# Accelerometer_revb.net
KiCad netlist of a schematic drawn in EAGLE
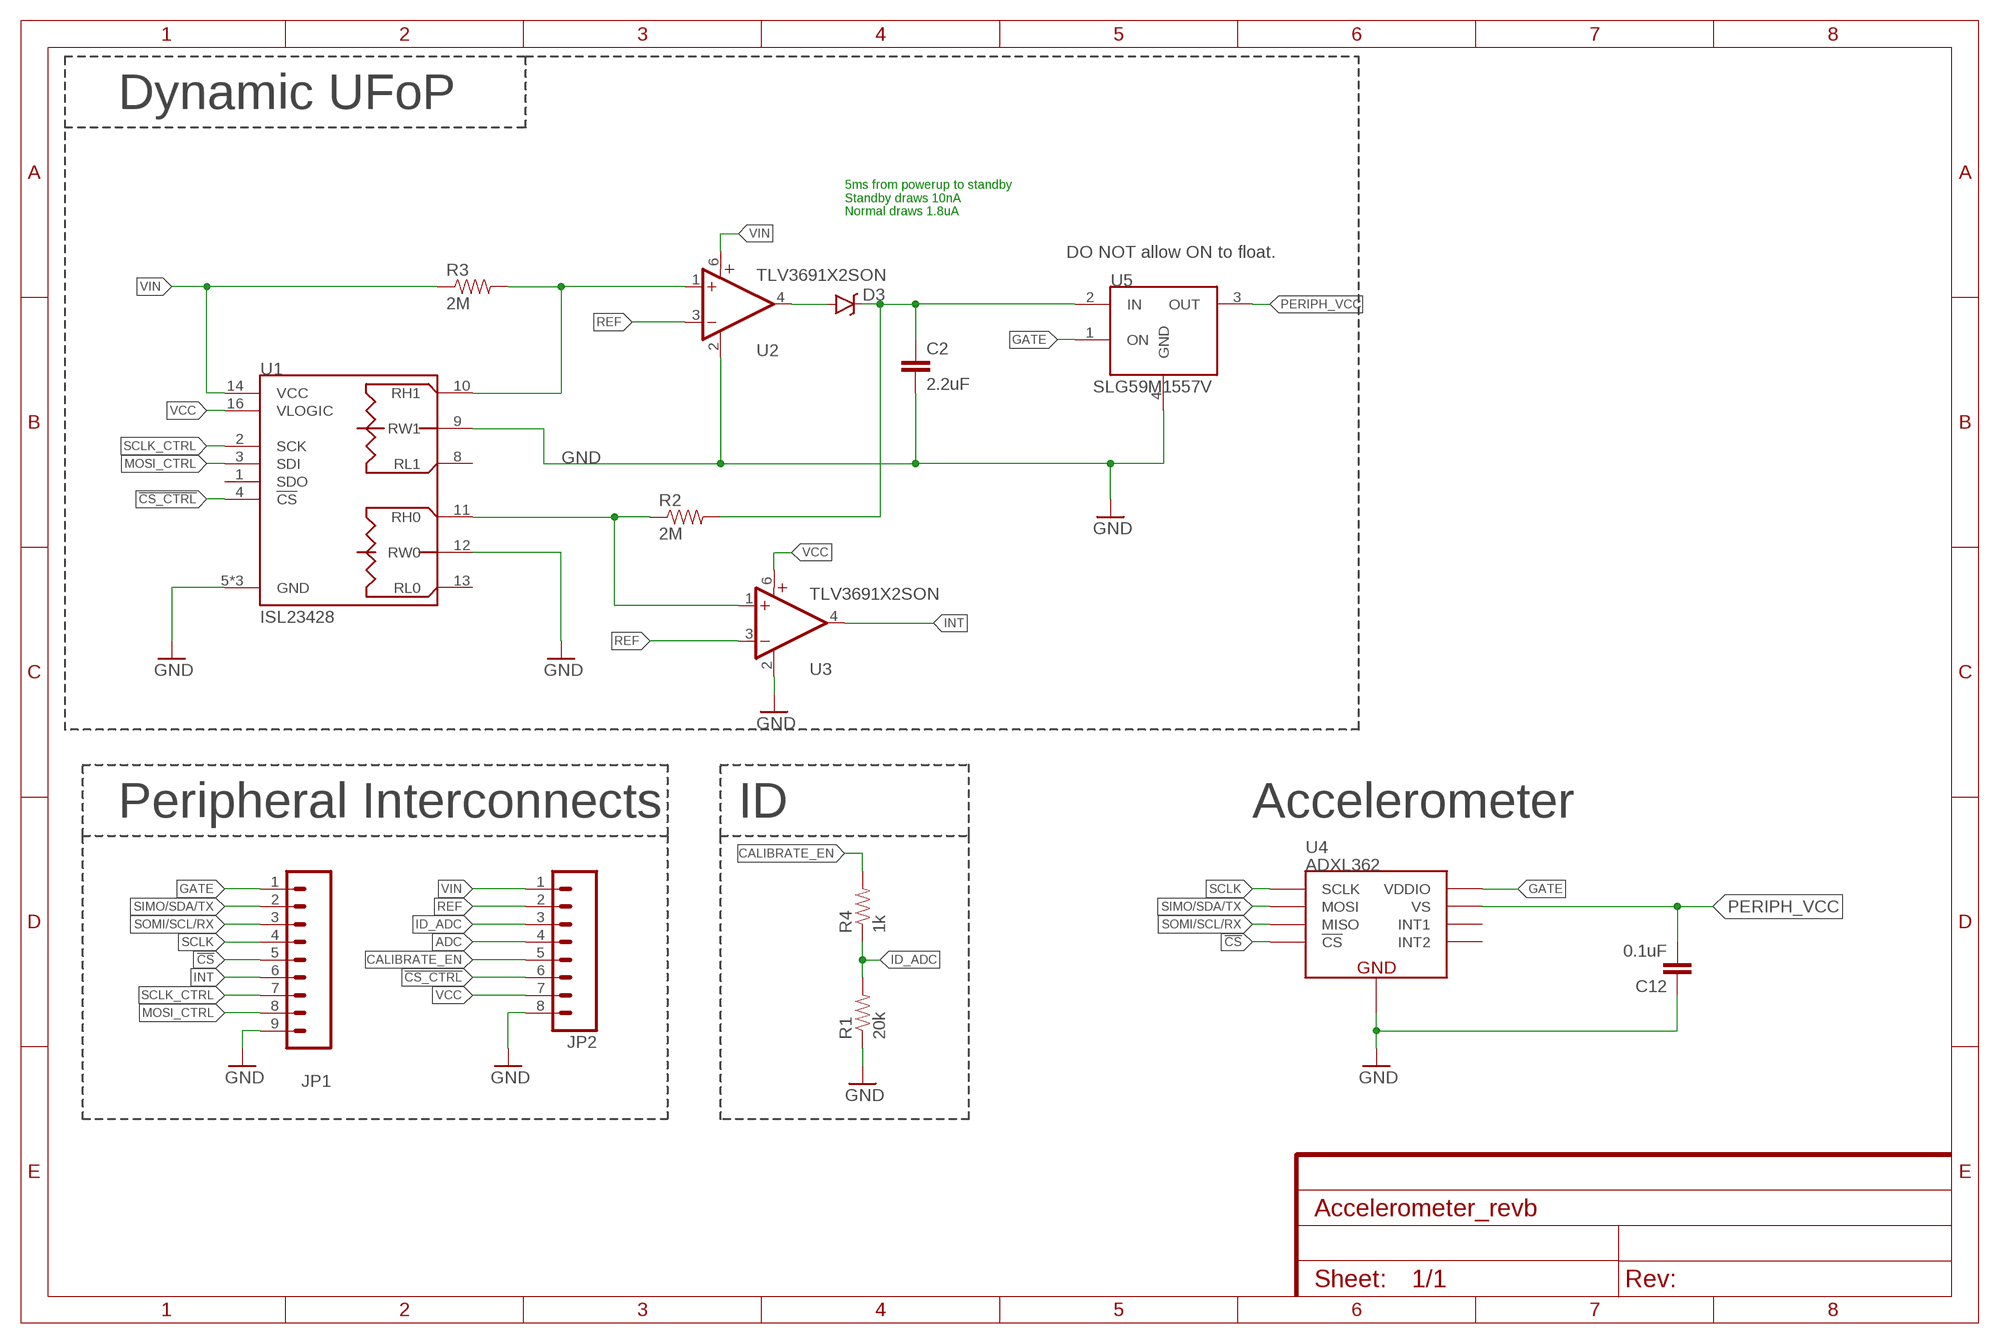
[diagram p0: schematic, sheet 1]

(export (version "E")
  (design (tool "Eeschema 10.0.6"))
  (components
    (comp (ref "C2")
      (value "2.2uF")
      (footprint "eagle-import:0603")
      (fields (field (name "MPN") "EMK107BJ225KA-T "))
      (libsource (lib "eagle-import") (part "C-EU0603"))
    )
    (comp (ref "C12")
      (value "0.1uF")
      (footprint "eagle-import:0402")
      (fields (field (name "MANAFACTURERPARTNUMBER") "  0402YD104KAT2A"))
      (libsource (lib "eagle-import") (part "C-EU"))
    )
    (comp (ref "D3")
      (value "RB751")
      (footprint "eagle-import:SOD-523")
      (fields (field (name "MPN") "BAS40-02V-V-G-08"))
      (libsource (lib "eagle-import") (part "DIODE-SCHOTTKY-RB751"))
    )
    (comp (ref "JP1")
      (value "M091.27MM")
      (footprint "eagle-import:1X09-1.27MM")
      (fields (field (name "MANUFACTURERPARTNUMBER") "GRPB091VWVN-RC ") (field (name "MPN") "GRPB091VWVN-RC"))
      (libsource (lib "eagle-import") (part "M091.27MM"))
    )
    (comp (ref "JP2")
      (value "M081.27MM")
      (footprint "eagle-import:1X08-1.27MM")
      (fields (field (name "MANUFACTURERPARTNUMBER") "GRPB081VWVN-RC "))
      (libsource (lib "eagle-import") (part "M081.27MM"))
    )
    (comp (ref "R1")
      (value "20k")
      (footprint "eagle-import:0402")
      (fields (field (name "MPN") "ERJ-2RKF2002X"))
      (libsource (lib "eagle-import") (part "R-EU"))
    )
    (comp (ref "R2")
      (value "2M")
      (footprint "eagle-import:0402")
      (fields (field (name "MPN") "RC1005F205CS"))
      (libsource (lib "eagle-import") (part "R-EU"))
    )
    (comp (ref "R3")
      (value "2M")
      (footprint "eagle-import:0402")
      (fields (field (name "MPN") "RC1005F205CS"))
      (libsource (lib "eagle-import") (part "R-EU"))
    )
    (comp (ref "R4")
      (value "1k")
      (footprint "eagle-import:0402")
      (fields (field (name "MPN") "ERJ-2RKF1001X"))
      (libsource (lib "eagle-import") (part "R-EU"))
    )
    (comp (ref "U1")
      (value "ISL23428")
      (footprint "eagle-import:UTQFN-16")
      (fields (field (name "MPN") "ISL23428TFRUZ-T7A"))
      (libsource (lib "eagle-import") (part "ISL23428"))
    )
    (comp (ref "U2")
      (value "TLV3691X2SON")
      (footprint "eagle-import:X2SON")
      (fields (field (name "MPN") "TLV3691IDPFR"))
      (libsource (lib "eagle-import") (part "TLV3691X2SON"))
    )
    (comp (ref "U3")
      (value "TLV3691X2SON")
      (footprint "eagle-import:X2SON")
      (fields (field (name "MPN") "TLV3691IDPFR"))
      (libsource (lib "eagle-import") (part "TLV3691X2SON"))
    )
    (comp (ref "U4")
      (value "ADXL362")
      (footprint "eagle-import:ADXL362")
      (fields (field (name "MPN") "ADXL362BCCZ-RL7 "))
      (libsource (lib "eagle-import") (part "ADXL362"))
    )
    (comp (ref "U5")
      (value "SLG59M1557V")
      (footprint "eagle-import:4STDFN")
      (fields (field (name "MPN") "SLG59M1557V "))
      (libsource (lib "eagle-import") (part "SLG59M1557V"))
    )
  )
  (nets
    (net (code "1") (name "/~{CS_CTRL}") (class "Default")
      (node (ref "JP2") (pin "6") (pinfunction "6_6") (pintype "passive"))
      (node (ref "U1") (pin "4") (pinfunction "~{CS}_4") (pintype "bidirectional"))
    )
    (net (code "2") (name "/~{CS}") (class "Default")
      (node (ref "JP1") (pin "5") (pinfunction "5_5") (pintype "passive"))
      (node (ref "U4") (pin "P$8") (pinfunction "~{CS}_P$8") (pintype "bidirectional"))
    )
    (net (code "3") (name "ADC") (class "Default")
      (node (ref "JP2") (pin "4") (pinfunction "4_4") (pintype "passive"))
    )
    (net (code "4") (name "CALIBRATE_EN") (class "Default")
      (node (ref "JP2") (pin "5") (pinfunction "5_5") (pintype "passive"))
      (node (ref "R4") (pin "2") (pinfunction "2_2") (pintype "passive"))
    )
    (net (code "5") (name "GATE") (class "Default")
      (node (ref "JP1") (pin "1") (pinfunction "1_1") (pintype "passive"))
      (node (ref "U4") (pin "P$1") (pinfunction "VDDIO_P$1") (pintype "bidirectional"))
      (node (ref "U5") (pin "1") (pinfunction "ON_1") (pintype "bidirectional"))
    )
    (net (code "6") (name "GND") (class "Default")
      (node (ref "C12") (pin "1") (pinfunction "1_1") (pintype "passive"))
      (node (ref "C2") (pin "2") (pinfunction "2_2") (pintype "passive"))
      (node (ref "JP1") (pin "9") (pinfunction "9_9") (pintype "passive"))
      (node (ref "JP2") (pin "8") (pinfunction "8_8") (pintype "passive"))
      (node (ref "R1") (pin "1") (pinfunction "1_1") (pintype "passive"))
      (node (ref "U1") (pin "12") (pinfunction "RW0_12") (pintype "bidirectional"))
      (node (ref "U1") (pin "15") (pinfunction "GND_15") (pintype "bidirectional"))
      (node (ref "U1") (pin "5") (pinfunction "GND_5") (pintype "bidirectional"))
      (node (ref "U1") (pin "6") (pinfunction "GND_6") (pintype "bidirectional"))
      (node (ref "U1") (pin "9") (pinfunction "RW1_9") (pintype "bidirectional"))
      (node (ref "U2") (pin "2") (pinfunction "GND_2") (pintype "power_in"))
      (node (ref "U3") (pin "2") (pinfunction "GND_2") (pintype "power_in"))
      (node (ref "U4") (pin "P$12") (pinfunction "GND_P$12") (pintype "bidirectional"))
      (node (ref "U4") (pin "P$13") (pinfunction "GND_P$13") (pintype "bidirectional"))
      (node (ref "U4") (pin "P$16") (pinfunction "GND_P$16") (pintype "bidirectional"))
      (node (ref "U5") (pin "4") (pinfunction "GND_4") (pintype "bidirectional"))
    )
    (net (code "7") (name "ID_ADC") (class "Default")
      (node (ref "JP2") (pin "3") (pinfunction "3_3") (pintype "passive"))
      (node (ref "R1") (pin "2") (pinfunction "2_2") (pintype "passive"))
      (node (ref "R4") (pin "1") (pinfunction "1_1") (pintype "passive"))
    )
    (net (code "8") (name "INT") (class "Default")
      (node (ref "JP1") (pin "6") (pinfunction "6_6") (pintype "passive"))
      (node (ref "U3") (pin "4") (pinfunction "OUT_4") (pintype "output"))
    )
    (net (code "9") (name "MOSI_CTRL") (class "Default")
      (node (ref "JP1") (pin "8") (pinfunction "8_8") (pintype "passive"))
      (node (ref "U1") (pin "3") (pinfunction "SDI_3") (pintype "bidirectional"))
    )
    (net (code "10") (name "Net-(U1-RH0)") (class "Default")
      (node (ref "R2") (pin "1") (pinfunction "1_1") (pintype "passive"))
      (node (ref "U1") (pin "11") (pinfunction "RH0_11") (pintype "bidirectional"))
      (node (ref "U3") (pin "1") (pinfunction "+IN_1") (pintype "input"))
    )
    (net (code "11") (name "Net-(U1-RH1)") (class "Default")
      (node (ref "R3") (pin "2") (pinfunction "2_2") (pintype "passive"))
      (node (ref "U1") (pin "10") (pinfunction "RH1_10") (pintype "bidirectional"))
      (node (ref "U2") (pin "1") (pinfunction "+IN_1") (pintype "input"))
    )
    (net (code "12") (name "Net-(U2-OUT)") (class "Default")
      (node (ref "D3") (pin "A") (pinfunction "A_A") (pintype "passive"))
      (node (ref "U2") (pin "4") (pinfunction "OUT_4") (pintype "output"))
    )
    (net (code "13") (name "Net-(U5-IN)") (class "Default")
      (node (ref "C2") (pin "1") (pinfunction "1_1") (pintype "passive"))
      (node (ref "D3") (pin "C") (pinfunction "C_C") (pintype "passive"))
      (node (ref "R2") (pin "2") (pinfunction "2_2") (pintype "passive"))
      (node (ref "U5") (pin "2") (pinfunction "IN_2") (pintype "bidirectional"))
    )
    (net (code "14") (name "PERIPH_VCC") (class "Default")
      (node (ref "C12") (pin "2") (pinfunction "2_2") (pintype "passive"))
      (node (ref "U4") (pin "P$14") (pinfunction "VS_P$14") (pintype "bidirectional"))
      (node (ref "U5") (pin "3") (pinfunction "OUT_3") (pintype "bidirectional"))
    )
    (net (code "15") (name "REF") (class "Default")
      (node (ref "JP2") (pin "2") (pinfunction "2_2") (pintype "passive"))
      (node (ref "U2") (pin "3") (pinfunction "-IN_3") (pintype "input"))
      (node (ref "U3") (pin "3") (pinfunction "-IN_3") (pintype "input"))
    )
    (net (code "16") (name "SCLK") (class "Default")
      (node (ref "JP1") (pin "4") (pinfunction "4_4") (pintype "passive"))
      (node (ref "U4") (pin "P$4") (pinfunction "SCLK_P$4") (pintype "bidirectional"))
    )
    (net (code "17") (name "SCLK_CTRL") (class "Default")
      (node (ref "JP1") (pin "7") (pinfunction "7_7") (pintype "passive"))
      (node (ref "U1") (pin "2") (pinfunction "SCK_2") (pintype "bidirectional"))
    )
    (net (code "18") (name "SIMO{slash}SDA{slash}TX") (class "Default")
      (node (ref "JP1") (pin "2") (pinfunction "2_2") (pintype "passive"))
      (node (ref "U4") (pin "P$6") (pinfunction "MOSI_P$6") (pintype "bidirectional"))
    )
    (net (code "19") (name "SOMI{slash}SCL{slash}RX") (class "Default")
      (node (ref "JP1") (pin "3") (pinfunction "3_3") (pintype "passive"))
      (node (ref "U4") (pin "P$7") (pinfunction "MISO_P$7") (pintype "bidirectional"))
    )
    (net (code "20") (name "VCC") (class "Default")
      (node (ref "JP2") (pin "7") (pinfunction "7_7") (pintype "passive"))
      (node (ref "U1") (pin "16") (pinfunction "VLOGIC_16") (pintype "bidirectional"))
      (node (ref "U3") (pin "6") (pinfunction "V+_6") (pintype "power_in"))
    )
    (net (code "21") (name "VIN") (class "Default")
      (node (ref "JP2") (pin "1") (pinfunction "1_1") (pintype "passive"))
      (node (ref "R3") (pin "1") (pinfunction "1_1") (pintype "passive"))
      (node (ref "U1") (pin "14") (pinfunction "VCC_14") (pintype "bidirectional"))
      (node (ref "U2") (pin "6") (pinfunction "V+_6") (pintype "power_in"))
    )
    (net (code "22") (name "unconnected-(U1-RL0-Pad13)") (class "Default")
      (node (ref "U1") (pin "13") (pinfunction "RL0_13") (pintype "bidirectional"))
    )
    (net (code "23") (name "unconnected-(U1-RL1-Pad8)") (class "Default")
      (node (ref "U1") (pin "8") (pinfunction "RL1_8") (pintype "bidirectional"))
    )
    (net (code "24") (name "unconnected-(U1-SDO-Pad1)") (class "Default")
      (node (ref "U1") (pin "1") (pinfunction "SDO_1") (pintype "bidirectional"))
    )
    (net (code "25") (name "unconnected-(U4-INT1-PadP$11)") (class "Default")
      (node (ref "U4") (pin "P$11") (pinfunction "INT1_P$11") (pintype "bidirectional"))
    )
    (net (code "26") (name "unconnected-(U4-INT2-PadP$9)") (class "Default")
      (node (ref "U4") (pin "P$9") (pinfunction "INT2_P$9") (pintype "bidirectional"))
    )
  )
)
